# foc.net
KiCad netlist of a schematic drawn in EasyEDA Pro
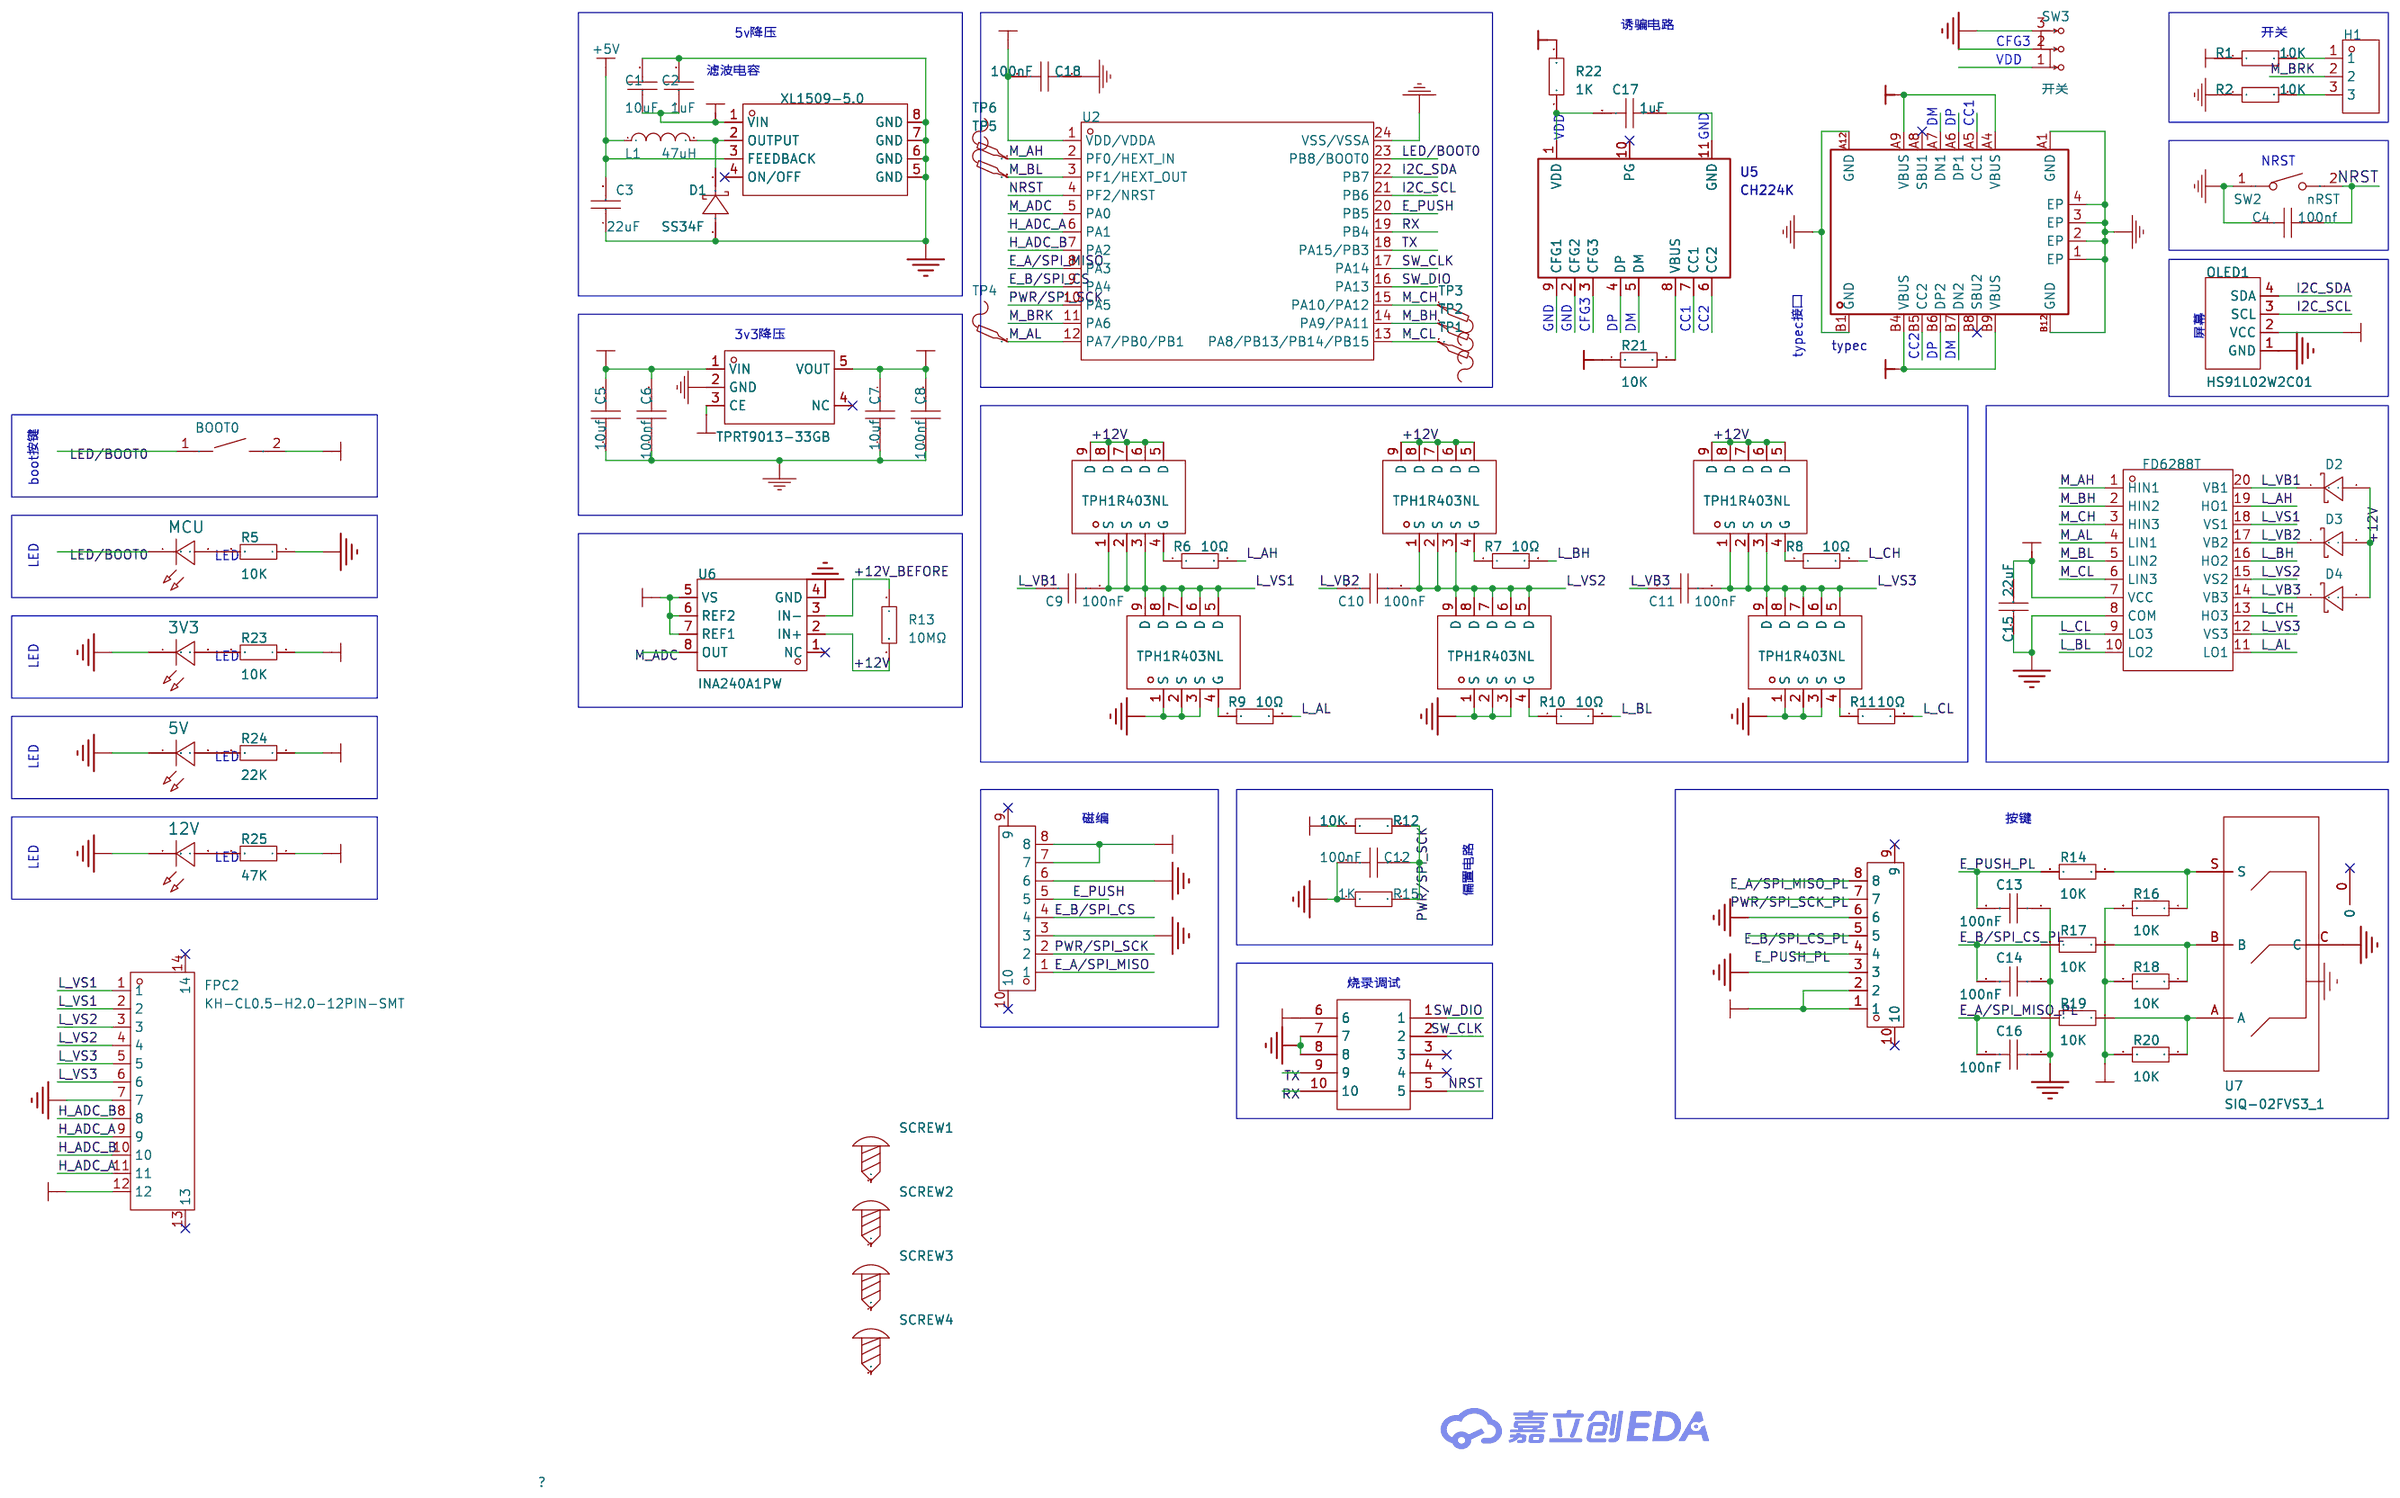
[diagram p0: schematic sheet]

(export (version "E")
  (design (tool "Eeschema 10.0.6"))
  (components
    (comp (ref "3V3")
      (value "~")
      (footprint "easyedapro:LED_0603")
      (libsource (lib "easyedapro") (part "LED_R"))
    )
    (comp (ref "5V")
      (value "~")
      (footprint "easyedapro:LED_0603")
      (libsource (lib "easyedapro") (part "LED_R"))
    )
    (comp (ref "12V")
      (value "~")
      (footprint "easyedapro:LED_0603")
      (libsource (lib "easyedapro") (part "LED_R"))
    )
    (comp (ref "BOOT0")
      (value "轻触按键3*4*H")
      (footprint "easyedapro:SW-SMD_L4.0-W2.9-LS5.0")
      (libsource (lib "") (part "轻触按键3*4*H_1"))
    )
    (comp (ref "C1")
      (value "10uF")
      (footprint "easyedapro:C1206")
      (description "容值:10uF;精度:±10%;额定电压:50V;材质(温度系数):X5R;")
      (fields
        (field (name "Manufacturer Part") "CL31A106KBHNNNE")
        (field (name "Manufacturer") "SAMSUNG(三星)")
      )
      (libsource (lib "easyedapro") (part "CL31A106KBHNNNE"))
    )
    (comp (ref "C2")
      (value "1uF")
      (fields
        (field (name "Manufacturer Part") "CL10A105KB8NNNC")
        (field (name "Manufacturer") "SAMSUNG(三星)")
      )
      (libsource (lib "easyedapro") (part "cl21b105kbfnnne"))
    )
    (comp (ref "C3")
      (value "22uF")
      (fields
        (field (name "Manufacturer Part") "CGA1206X5R226M350NT")
        (field (name "Manufacturer") "HRE(芯声)")
      )
      (libsource (lib "easyedapro") (part "cl21a476mqynnne"))
    )
    (comp (ref "C4")
      (value "100nf")
      (footprint "easyedapro:C0603")
      (libsource (lib "easyedapro") (part "100nf"))
    )
    (comp (ref "C5")
      (value "10uf")
      (footprint "easyedapro:C1206")
      (description "容值:10uF;精度:±10%;额定电压:50V;温度系数:X5R;")
      (fields
        (field (name "Manufacturer Part") "HGC1206R5106K500NSPJ")
        (field (name "Manufacturer") "Chinocera(华瓷)")
      )
      (libsource (lib "easyedapro") (part "HGC1206R5106K500NSPJ"))
    )
    (comp (ref "C6")
      (value "100nf")
      (footprint "easyedapro:C0603")
      (libsource (lib "easyedapro") (part "100nf"))
    )
    (comp (ref "C7")
      (value "10uf")
      (footprint "easyedapro:C1206")
      (description "容值:10uF;精度:±10%;额定电压:50V;温度系数:X5R;")
      (fields
        (field (name "Manufacturer Part") "HGC1206R5106K500NSPJ")
        (field (name "Manufacturer") "Chinocera(华瓷)")
      )
      (libsource (lib "easyedapro") (part "HGC1206R5106K500NSPJ"))
    )
    (comp (ref "C8")
      (value "100nf")
      (footprint "easyedapro:C0603")
      (libsource (lib "easyedapro") (part "100nf"))
    )
    (comp (ref "C9")
      (value "100nF")
      (footprint "easyedapro:C0603")
      (description "容值:100nF;精度:±10%;额定电压:50V;材质(温度系数):X7R;")
      (fields
        (field (name "Manufacturer Part") "CC0603KRX7R9BB104")
        (field (name "Manufacturer") "YAGEO(国巨)")
      )
      (libsource (lib "easyedapro") (part "CC0603KRX7R9BB104"))
    )
    (comp (ref "C10")
      (value "100nF")
      (footprint "easyedapro:C0603")
      (description "容值:100nF;精度:±10%;额定电压:50V;材质(温度系数):X7R;")
      (fields
        (field (name "Manufacturer Part") "CC0603KRX7R9BB104")
        (field (name "Manufacturer") "YAGEO(国巨)")
      )
      (libsource (lib "easyedapro") (part "CC0603KRX7R9BB104"))
    )
    (comp (ref "C11")
      (value "100nF")
      (footprint "easyedapro:C0603")
      (description "容值:100nF;精度:±10%;额定电压:50V;材质(温度系数):X7R;")
      (fields
        (field (name "Manufacturer Part") "CC0603KRX7R9BB104")
        (field (name "Manufacturer") "YAGEO(国巨)")
      )
      (libsource (lib "easyedapro") (part "CC0603KRX7R9BB104"))
    )
    (comp (ref "C12")
      (value "100nF")
      (footprint "easyedapro:C0603")
      (libsource (lib "easyedapro") (part "CapAcitance"))
    )
    (comp (ref "C13")
      (value "100nF")
      (footprint "easyedapro:C0603")
      (libsource (lib "easyedapro") (part "CapAcitance"))
    )
    (comp (ref "C14")
      (value "100nF")
      (footprint "easyedapro:C0603")
      (libsource (lib "easyedapro") (part "CapAcitance"))
    )
    (comp (ref "C15")
      (value "22uF")
      (fields
        (field (name "Manufacturer Part") "CGA0805X5R226M350MT")
        (field (name "Manufacturer") "HRE(芯声)")
      )
      (libsource (lib "easyedapro") (part "cc0805krx7r9bb104"))
    )
    (comp (ref "C16")
      (value "100nF")
      (footprint "easyedapro:C0603")
      (libsource (lib "easyedapro") (part "CapAcitance"))
    )
    (comp (ref "C17")
      (value "1uF")
      (footprint "easyedapro:C0603")
      (libsource (lib "easyedapro") (part "CapAcitance"))
    )
    (comp (ref "C18")
      (value "100nF")
      (footprint "easyedapro:C0603")
      (libsource (lib "easyedapro") (part "CapAcitance"))
    )
    (comp (ref "D1")
      (value "SS34F")
      (footprint "easyedapro:SMAF_L3.5-W2.6-LS4.7-FD")
      (description "二极管配置:独立式;正向压降(Vf):550mV@3A;直流反向耐压(Vr):40V;平均整流电流(Io):3A;")
      (fields (field (name "Manufacturer") "FUXINSEMI(富芯森美)"))
      (libsource (lib "easyedapro") (part "SS34F_C908239"))
    )
    (comp (ref "D2")
      (value "1N5819WS")
      (footprint "easyedapro:SOD-323_L1.8-W1.3-LS2.5-RD")
      (description "正向压降(Vf):600mV@1A;直流反向耐压(Vr):40V;平均整流电流(Io):1A;")
      (fields (field (name "Manufacturer") "Hottech(合科泰)"))
      (libsource (lib "easyedapro") (part "1N5819WS"))
    )
    (comp (ref "D3")
      (value "1N5819WS")
      (footprint "easyedapro:SOD-323_L1.8-W1.3-LS2.5-RD")
      (description "正向压降(Vf):600mV@1A;直流反向耐压(Vr):40V;平均整流电流(Io):1A;")
      (fields (field (name "Manufacturer") "Hottech(合科泰)"))
      (libsource (lib "easyedapro") (part "1N5819WS"))
    )
    (comp (ref "D4")
      (value "1N5819WS")
      (footprint "easyedapro:SOD-323_L1.8-W1.3-LS2.5-RD")
      (description "正向压降(Vf):600mV@1A;直流反向耐压(Vr):40V;平均整流电流(Io):1A;")
      (fields (field (name "Manufacturer") "Hottech(合科泰)"))
      (libsource (lib "easyedapro") (part "1N5819WS"))
    )
    (comp (ref "FPC1")
      (value "FPC-05F-8PH20")
      (footprint "easyedapro:FPC-SMD_8P-P0.50_FPC-05F-8PH20")
      (description "锁定特性:翻盖式;触点类型:下接;触点数量:8P;间距:0.5mm;安装类型:卧贴;工作温度范围:-25°C~+85°C;")
      (fields (field (name "Manufacturer") "XUNPU(讯普)"))
      (libsource (lib "easyedapro") (part "FPC-05F-8PH20"))
    )
    (comp (ref "FPC2")
      (value "KH-CL0.5-H2.0-12PIN-SMT")
      (footprint "easyedapro:FPC-SMD_12P-P0.50_KH-CL0.5-H2.0-12PIN-SMT")
      (description "锁定特性:抽屉式;触点类型:下接;触点数量:12P;间距:0.5mm;")
      (fields (field (name "Manufacturer") "kinghelm(金航标)"))
      (libsource (lib "easyedapro") (part "KH-CL0.5-H2.0-12PIN-SMT"))
    )
    (comp (ref "FPC3")
      (value "FPC-05F-8PH20")
      (footprint "easyedapro:FPC-SMD_8P-P0.50_FPC-05F-8PH20")
      (description "锁定特性:翻盖式;触点类型:下接;触点数量:8P;间距:0.5mm;安装类型:卧贴;工作温度范围:-25°C~+85°C;")
      (fields (field (name "Manufacturer") "XUNPU(讯普)"))
      (libsource (lib "easyedapro") (part "FPC-05F-8PH20"))
    )
    (comp (ref "H1")
      (value "~")
      (footprint "easyedapro:HDR-TH_3P-P2.54-V-M")
      (libsource (lib "easyedapro") (part "PZ254V-11-03P_C2937625"))
    )
    (comp (ref "L1")
      (value "47uH")
      (fields (field (name "Manufacturer Part") "FXL0630-470-M") (field (name "Manufacturer") "cjiang(长江微电)"))
      (libsource (lib "easyedapro") (part "mscd32-470kt"))
    )
    (comp (ref "MCU")
      (value "~")
      (footprint "easyedapro:LED_0603")
      (libsource (lib "easyedapro") (part "LED_R"))
    )
    (comp (ref "OLED1")
      (value "HS91L02W2C01")
      (footprint "easyedapro:OLED-TH_L38.0-W12.0_HS91L02W2C01")
      (description "主控芯片:SSD1306;接口类型:I2C;尺寸(inch):0.91;像素分辨率:128x32;")
      (fields (field (name "Manufacturer") "HS(汉昇)"))
      (libsource (lib "easyedapro") (part "HS91L02W2C01"))
    )
    (comp (ref "P1")
      (value "~")
      (footprint "easyedapro:PAD_S_2.54_2*5")
      (libsource (lib "easyedapro") (part "PAD_S_2.54_2*5"))
    )
    (comp (ref "Q1")
      (value "TPH1R403NL")
      (footprint "easyedapro:DSOP-8_L5.0-W5.0-P1.27-LS6.0-BL-EP")
      (fields (field (name "Manufacturer") "TOSHIBA(东芝)"))
      (libsource (lib "easyedapro") (part "TPH1R403NL"))
    )
    (comp (ref "Q2")
      (value "TPH1R403NL")
      (footprint "easyedapro:DSOP-8_L5.0-W5.0-P1.27-LS6.0-BL-EP")
      (fields (field (name "Manufacturer") "TOSHIBA(东芝)"))
      (libsource (lib "easyedapro") (part "TPH1R403NL"))
    )
    (comp (ref "Q3")
      (value "TPH1R403NL")
      (footprint "easyedapro:DSOP-8_L5.0-W5.0-P1.27-LS6.0-BL-EP")
      (fields (field (name "Manufacturer") "TOSHIBA(东芝)"))
      (libsource (lib "easyedapro") (part "TPH1R403NL"))
    )
    (comp (ref "Q4")
      (value "TPH1R403NL")
      (footprint "easyedapro:DSOP-8_L5.0-W5.0-P1.27-LS6.0-BL-EP")
      (fields (field (name "Manufacturer") "TOSHIBA(东芝)"))
      (libsource (lib "easyedapro") (part "TPH1R403NL"))
    )
    (comp (ref "Q5")
      (value "TPH1R403NL")
      (footprint "easyedapro:DSOP-8_L5.0-W5.0-P1.27-LS6.0-BL-EP")
      (fields (field (name "Manufacturer") "TOSHIBA(东芝)"))
      (libsource (lib "easyedapro") (part "TPH1R403NL"))
    )
    (comp (ref "Q6")
      (value "TPH1R403NL")
      (footprint "easyedapro:DSOP-8_L5.0-W5.0-P1.27-LS6.0-BL-EP")
      (fields (field (name "Manufacturer") "TOSHIBA(东芝)"))
      (libsource (lib "easyedapro") (part "TPH1R403NL"))
    )
    (comp (ref "R1") (value "10K") (footprint "easyedapro:R0603") (libsource (lib "easyedapro") (part "电阻")))
    (comp (ref "R2") (value "10K") (footprint "easyedapro:R0603") (libsource (lib "easyedapro") (part "电阻")))
    (comp (ref "R5") (value "10K") (footprint "easyedapro:R0603") (libsource (lib "easyedapro") (part "电阻")))
    (comp (ref "R6")
      (value "10Ω")
      (footprint "easyedapro:R0603")
      (description "电阻类型:厚膜电阻;阻值:10Ω;精度:±1%;功率:100mW;最大工作电压:75V;温度系数:±400ppm/°C;")
      (fields
        (field (name "Manufacturer Part") "0603WAF100JT5E")
        (field (name "Manufacturer") "UNI-ROYAL(厚声)")
      )
      (libsource (lib "easyedapro") (part "0603WAF100JT5E"))
    )
    (comp (ref "R7")
      (value "10Ω")
      (footprint "easyedapro:R0603")
      (description "电阻类型:厚膜电阻;阻值:10Ω;精度:±1%;功率:100mW;最大工作电压:75V;温度系数:±400ppm/°C;")
      (fields
        (field (name "Manufacturer Part") "0603WAF100JT5E")
        (field (name "Manufacturer") "UNI-ROYAL(厚声)")
      )
      (libsource (lib "easyedapro") (part "0603WAF100JT5E"))
    )
    (comp (ref "R8")
      (value "10Ω")
      (footprint "easyedapro:R0603")
      (description "电阻类型:厚膜电阻;阻值:10Ω;精度:±1%;功率:100mW;最大工作电压:75V;温度系数:±400ppm/°C;")
      (fields
        (field (name "Manufacturer Part") "0603WAF100JT5E")
        (field (name "Manufacturer") "UNI-ROYAL(厚声)")
      )
      (libsource (lib "easyedapro") (part "0603WAF100JT5E"))
    )
    (comp (ref "R9")
      (value "10Ω")
      (footprint "easyedapro:R0603")
      (description "电阻类型:厚膜电阻;阻值:10Ω;精度:±1%;功率:100mW;最大工作电压:75V;温度系数:±400ppm/°C;")
      (fields
        (field (name "Manufacturer Part") "0603WAF100JT5E")
        (field (name "Manufacturer") "UNI-ROYAL(厚声)")
      )
      (libsource (lib "easyedapro") (part "0603WAF100JT5E"))
    )
    (comp (ref "R10")
      (value "10Ω")
      (footprint "easyedapro:R0603")
      (description "电阻类型:厚膜电阻;阻值:10Ω;精度:±1%;功率:100mW;最大工作电压:75V;温度系数:±400ppm/°C;")
      (fields
        (field (name "Manufacturer Part") "0603WAF100JT5E")
        (field (name "Manufacturer") "UNI-ROYAL(厚声)")
      )
      (libsource (lib "easyedapro") (part "0603WAF100JT5E"))
    )
    (comp (ref "R11")
      (value "10Ω")
      (footprint "easyedapro:R0603")
      (description "电阻类型:厚膜电阻;阻值:10Ω;精度:±1%;功率:100mW;最大工作电压:75V;温度系数:±400ppm/°C;")
      (fields
        (field (name "Manufacturer Part") "0603WAF100JT5E")
        (field (name "Manufacturer") "UNI-ROYAL(厚声)")
      )
      (libsource (lib "easyedapro") (part "0603WAF100JT5E"))
    )
    (comp (ref "R12") (value "10K") (footprint "easyedapro:R0603") (libsource (lib "easyedapro") (part "电阻")))
    (comp (ref "R13")
      (value "10MΩ")
      (footprint "easyedapro:R2512")
      (description "电阻类型:厚膜电阻;阻值:10MΩ;精度:±5%;功率:1W;工作电压:200V;温度系数:±100ppm/°C;")
      (fields
        (field (name "Manufacturer Part") "CR2512J10M0E04Z")
        (field (name "Manufacturer") "EVER OHMS(天二科技)")
      )
      (libsource (lib "easyedapro") (part "CR2512J10ME04"))
    )
    (comp (ref "R14")
      (value "10K")
      (footprint "easyedapro:R0603")
      (fields (field (name "Manufacturer Part") "ARG03FTC1002") (field (name "Manufacturer") "Viking Tech"))
      (libsource (lib "easyedapro") (part "10K"))
    )
    (comp (ref "R15") (value "1K") (footprint "easyedapro:R0603") (libsource (lib "easyedapro") (part "电阻")))
    (comp (ref "R16")
      (value "10K")
      (footprint "easyedapro:R0603")
      (fields (field (name "Manufacturer Part") "ARG03FTC1002") (field (name "Manufacturer") "Viking Tech"))
      (libsource (lib "easyedapro") (part "10K"))
    )
    (comp (ref "R17")
      (value "10K")
      (footprint "easyedapro:R0603")
      (fields (field (name "Manufacturer Part") "ARG03FTC1002") (field (name "Manufacturer") "Viking Tech"))
      (libsource (lib "easyedapro") (part "10K"))
    )
    (comp (ref "R18")
      (value "10K")
      (footprint "easyedapro:R0603")
      (fields (field (name "Manufacturer Part") "ARG03FTC1002") (field (name "Manufacturer") "Viking Tech"))
      (libsource (lib "easyedapro") (part "10K"))
    )
    (comp (ref "R19")
      (value "10K")
      (footprint "easyedapro:R0603")
      (fields (field (name "Manufacturer Part") "ARG03FTC1002") (field (name "Manufacturer") "Viking Tech"))
      (libsource (lib "easyedapro") (part "10K"))
    )
    (comp (ref "R20")
      (value "10K")
      (footprint "easyedapro:R0603")
      (fields (field (name "Manufacturer Part") "ARG03FTC1002") (field (name "Manufacturer") "Viking Tech"))
      (libsource (lib "easyedapro") (part "10K"))
    )
    (comp (ref "R21") (value "10K") (footprint "easyedapro:R0603") (libsource (lib "easyedapro") (part "电阻")))
    (comp (ref "R22") (value "1K") (footprint "easyedapro:R0603") (libsource (lib "easyedapro") (part "电阻")))
    (comp (ref "R23") (value "10K") (footprint "easyedapro:R0603") (libsource (lib "easyedapro") (part "电阻")))
    (comp (ref "R24") (value "22K") (footprint "easyedapro:R0603") (libsource (lib "easyedapro") (part "电阻")))
    (comp (ref "R25") (value "47K") (footprint "easyedapro:R0603") (libsource (lib "easyedapro") (part "电阻")))
    (comp (ref "SCREW1")
      (value "~")
      (footprint "easyedapro:M2螺丝")
      (libsource (lib "easyedapro") (part "螺丝孔"))
    )
    (comp (ref "SCREW2")
      (value "~")
      (footprint "easyedapro:M2螺丝")
      (libsource (lib "easyedapro") (part "螺丝孔"))
    )
    (comp (ref "SCREW3")
      (value "~")
      (footprint "easyedapro:M2螺丝")
      (libsource (lib "easyedapro") (part "螺丝孔"))
    )
    (comp (ref "SCREW4")
      (value "~")
      (footprint "easyedapro:M2螺丝")
      (libsource (lib "easyedapro") (part "螺丝孔"))
    )
    (comp (ref "SW2")
      (value "nRST")
      (fields (field (name "Manufacturer Part") "轻触按键3*4*H"))
      (libsource (lib "easyedapro") (part "轻触按键3*4*H"))
    )
    (comp (ref "SW3")
      (value "开关")
      (footprint "easyedapro:SW-TH_SS-12D01-GX")
      (libsource (lib "easyedapro") (part "开关"))
    )
    (comp (ref "TP1")
      (value "~")
      (footprint "easyedapro:Test-Point-0.5mm")
      (description "Test Point 测试点")
      (libsource (lib "easyedapro") (part "Test-Point"))
    )
    (comp (ref "TP2")
      (value "~")
      (footprint "easyedapro:Test-Point-0.5mm")
      (description "Test Point 测试点")
      (libsource (lib "easyedapro") (part "Test-Point"))
    )
    (comp (ref "TP3")
      (value "~")
      (footprint "easyedapro:Test-Point-0.5mm")
      (description "Test Point 测试点")
      (libsource (lib "easyedapro") (part "Test-Point"))
    )
    (comp (ref "TP4")
      (value "~")
      (footprint "easyedapro:Test-Point-0.5mm")
      (description "Test Point 测试点")
      (libsource (lib "easyedapro") (part "Test-Point"))
    )
    (comp (ref "TP5")
      (value "~")
      (footprint "easyedapro:Test-Point-0.5mm")
      (description "Test Point 测试点")
      (libsource (lib "easyedapro") (part "Test-Point"))
    )
    (comp (ref "TP6")
      (value "~")
      (footprint "easyedapro:Test-Point-0.5mm")
      (description "Test Point 测试点")
      (libsource (lib "easyedapro") (part "Test-Point"))
    )
    (comp (ref "U1")
      (value "XL1509-5.0")
      (footprint "easyedapro:SOIC-8_L4.9-W3.9-P1.27-LS6.0-TR")
      (fields (field (name "Manufacturer") "UMW(广东友台半导体)"))
      (libsource (lib "easyedapro") (part "XL1509-5.0_C2902368"))
    )
    (comp (ref "U2")
      (value "~")
      (footprint "easyedapro:TSSOP-24_L7.8-W4.4-P0.65-LS6.4-BL")
      (fields (field (name "Manufacturer") "Artery Technology"))
      (libsource (lib "easyedapro") (part "AT32M416ExP7"))
    )
    (comp (ref "U4")
      (value "TPRT9013-33GB")
      (footprint "easyedapro:SOT-23-5_L3.0-W1.7-P0.95-LS2.8-BL")
      (description "输出类型:-;")
      (fields (field (name "Manufacturer") "TECH PUBLIC(台舟)"))
      (libsource (lib "easyedapro") (part "TPRT9013-33GB"))
    )
    (comp (ref "U5")
      (value "CH224K")
      (footprint "easyedapro:ESSOP-10_L4.9-W3.9-P1.0-LS6.0-TL-EP")
      (fields (field (name "Manufacturer") "WCH(南京沁恒)"))
      (libsource (lib "easyedapro") (part "CH224K"))
    )
    (comp (ref "U6")
      (value "INA240A1PW")
      (footprint "easyedapro:TSSOP-8_L4.4-W3.0-P0.65-LS6.4-TL")
      (description "放大器数:单路;")
      (fields (field (name "Manufacturer") "TI(德州仪器)"))
      (libsource (lib "easyedapro") (part "INA240A1PW"))
    )
    (comp (ref "U7")
      (value "SIQ-02FVS3_1")
      (footprint "easyedapro:SW-SMD_SIQ-02FVS3_1")
      (libsource (lib "easyedapro") (part "SIQ-02FVS3_1"))
    )
    (comp (ref "U8")
      (value "FD6288T")
      (footprint "easyedapro:TSSOP-20_L6.5-W4.4-P0.65-LS6.4-BL")
      (description "驱动配置:高低侧;负载类型:MOSFET;峰值灌电流:1.5A;峰值拉电流:1.8A;电源电压:8V~20V;")
      (fields (field (name "Manufacturer") "JSMSEMI(杰盛微)"))
      (libsource (lib "easyedapro") (part "FD6288T"))
    )
    (comp (ref "USB1")
      (value "typec")
      (footprint "easyedapro:USB-C-SMD_KH-TYPE-C-16P")
      (libsource (lib "easyedapro") (part "TYPEC_C9900016956"))
    )
  )
  (nets
    (net (code "1") (name "+3V3") (class "Default")
      (node (ref "BOOT0") (pin "2") (pinfunction "2_2") (pintype "unspecified"))
      (node (ref "C18") (pin "1") (pinfunction "1_1") (pintype "input"))
      (node (ref "C7") (pin "1") (pinfunction "1_1") (pintype "unspecified"))
      (node (ref "C8") (pin "2") (pinfunction "2_2") (pintype "unspecified"))
      (node (ref "FPC1") (pin "7") (pinfunction "7_7") (pintype "unspecified"))
      (node (ref "FPC1") (pin "8") (pinfunction "8_8") (pintype "unspecified"))
      (node (ref "FPC2") (pin "12") (pinfunction "12_12") (pintype "unspecified"))
      (node (ref "OLED1") (pin "2") (pinfunction "VCC_2") (pintype "unspecified"))
      (node (ref "P1") (pin "6") (pinfunction "6_6") (pintype "input"))
      (node (ref "R1") (pin "1") (pinfunction "1_1") (pintype "input"))
      (node (ref "R23") (pin "1") (pinfunction "1_1") (pintype "input"))
      (node (ref "U2") (pin "1") (pinfunction "VDD/VDDA_1") (pintype "input"))
      (node (ref "U4") (pin "5") (pinfunction "VOUT_5") (pintype "input"))
      (node (ref "U6") (pin "5") (pinfunction "VS_5") (pintype "unspecified"))
      (node (ref "U6") (pin "6") (pinfunction "REF2_6") (pintype "unspecified"))
      (node (ref "U6") (pin "7") (pinfunction "REF1_7") (pintype "unspecified"))
    )
    (net (code "2") (name "+3V3_PL") (class "Default")
      (node (ref "FPC3") (pin "1") (pinfunction "1_1") (pintype "unspecified"))
      (node (ref "FPC3") (pin "2") (pinfunction "2_2") (pintype "unspecified"))
      (node (ref "R16") (pin "2") (pinfunction "2_2") (pintype "unspecified"))
      (node (ref "R18") (pin "2") (pinfunction "2_2") (pintype "unspecified"))
      (node (ref "R20") (pin "2") (pinfunction "2_2") (pintype "unspecified"))
    )
    (net (code "3") (name "+5V") (class "Default")
      (node (ref "C3") (pin "2") (pinfunction "2_2") (pintype "input"))
      (node (ref "C5") (pin "1") (pinfunction "1_1") (pintype "unspecified"))
      (node (ref "C6") (pin "2") (pinfunction "2_2") (pintype "unspecified"))
      (node (ref "L1") (pin "1") (pinfunction "1_1") (pintype "unspecified"))
      (node (ref "R24") (pin "1") (pinfunction "1_1") (pintype "input"))
      (node (ref "U1") (pin "3") (pinfunction "FEEDBACK_3") (pintype "unspecified"))
      (node (ref "U4") (pin "1") (pinfunction "VIN_1") (pintype "input"))
      (node (ref "U4") (pin "3") (pinfunction "CE_3") (pintype "input"))
    )
    (net (code "4") (name "+12V") (class "Default")
      (node (ref "C1") (pin "1") (pinfunction "1_1") (pintype "input"))
      (node (ref "C15") (pin "2") (pinfunction "2_2") (pintype "input"))
      (node (ref "C2") (pin "1") (pinfunction "1_1") (pintype "input"))
      (node (ref "D2") (pin "2") (pinfunction "A_2") (pintype "unspecified"))
      (node (ref "D3") (pin "2") (pinfunction "A_2") (pintype "unspecified"))
      (node (ref "D4") (pin "2") (pinfunction "A_2") (pintype "unspecified"))
      (node (ref "Q1") (pin "5") (pinfunction "D_5") (pintype "unspecified"))
      (node (ref "Q1") (pin "6") (pinfunction "D_6") (pintype "unspecified"))
      (node (ref "Q1") (pin "7") (pinfunction "D_7") (pintype "unspecified"))
      (node (ref "Q1") (pin "8") (pinfunction "D_8") (pintype "unspecified"))
      (node (ref "Q1") (pin "9") (pinfunction "D_9") (pintype "unspecified"))
      (node (ref "Q2") (pin "5") (pinfunction "D_5") (pintype "unspecified"))
      (node (ref "Q2") (pin "6") (pinfunction "D_6") (pintype "unspecified"))
      (node (ref "Q2") (pin "7") (pinfunction "D_7") (pintype "unspecified"))
      (node (ref "Q2") (pin "8") (pinfunction "D_8") (pintype "unspecified"))
      (node (ref "Q2") (pin "9") (pinfunction "D_9") (pintype "unspecified"))
      (node (ref "Q3") (pin "5") (pinfunction "D_5") (pintype "unspecified"))
      (node (ref "Q3") (pin "6") (pinfunction "D_6") (pintype "unspecified"))
      (node (ref "Q3") (pin "7") (pinfunction "D_7") (pintype "unspecified"))
      (node (ref "Q3") (pin "8") (pinfunction "D_8") (pintype "unspecified"))
      (node (ref "Q3") (pin "9") (pinfunction "D_9") (pintype "unspecified"))
      (node (ref "R12") (pin "1") (pinfunction "1_1") (pintype "input"))
      (node (ref "R13") (pin "2") (pinfunction "2_2") (pintype "unspecified"))
      (node (ref "R25") (pin "1") (pinfunction "1_1") (pintype "input"))
      (node (ref "U1") (pin "1") (pinfunction "VIN_1") (pintype "unspecified"))
      (node (ref "U6") (pin "2") (pinfunction "IN+_2") (pintype "unspecified"))
      (node (ref "U8") (pin "7") (pinfunction "VCC_7") (pintype "unspecified"))
    )
    (net (code "5") (name "+12V_BEFORE") (class "Default")
      (node (ref "R13") (pin "1") (pinfunction "1_1") (pintype "unspecified"))
      (node (ref "R21") (pin "1") (pinfunction "1_1") (pintype "input"))
      (node (ref "R22") (pin "2") (pinfunction "2_2") (pintype "input"))
      (node (ref "U6") (pin "3") (pinfunction "IN-_3") (pintype "unspecified"))
      (node (ref "USB1") (pin "A4") (pinfunction "VBUS_A4") (pintype "unspecified"))
      (node (ref "USB1") (pin "A9") (pinfunction "VBUS_A9") (pintype "unspecified"))
      (node (ref "USB1") (pin "B4") (pinfunction "VBUS_B4") (pintype "unspecified"))
      (node (ref "USB1") (pin "B9") (pinfunction "VBUS_B9") (pintype "unspecified"))
    )
    (net (code "6") (name "/CC1") (class "Default")
      (node (ref "U5") (pin "7") (pinfunction "CC1_7") (pintype "unspecified"))
      (node (ref "USB1") (pin "A5") (pinfunction "CC1_A5") (pintype "unspecified"))
    )
    (net (code "7") (name "/CC2") (class "Default")
      (node (ref "U5") (pin "6") (pinfunction "CC2_6") (pintype "unspecified"))
      (node (ref "USB1") (pin "B5") (pinfunction "CC2_B5") (pintype "unspecified"))
    )
    (net (code "8") (name "/CFG3") (class "Default")
      (node (ref "SW3") (pin "2") (pinfunction "2_2") (pintype "unspecified"))
      (node (ref "U5") (pin "3") (pinfunction "CFG3_3") (pintype "unspecified"))
    )
    (net (code "9") (name "/DM") (class "Default")
      (node (ref "U5") (pin "5") (pinfunction "DM_5") (pintype "unspecified"))
      (node (ref "USB1") (pin "A7") (pinfunction "DN1_A7") (pintype "unspecified"))
      (node (ref "USB1") (pin "B7") (pinfunction "DN2_B7") (pintype "unspecified"))
    )
    (net (code "10") (name "/DP") (class "Default")
      (node (ref "U5") (pin "4") (pinfunction "DP_4") (pintype "unspecified"))
      (node (ref "USB1") (pin "A6") (pinfunction "DP1_A6") (pintype "unspecified"))
      (node (ref "USB1") (pin "B6") (pinfunction "DP2_B6") (pintype "unspecified"))
    )
    (net (code "11") (name "/E_A{slash}SPI_MISO") (class "Default")
      (node (ref "FPC1") (pin "1") (pinfunction "1_1") (pintype "unspecified"))
      (node (ref "U2") (pin "8") (pinfunction "PA3_8") (pintype "input"))
    )
    (net (code "12") (name "/E_A{slash}SPI_MISO_PL") (class "Default")
      (node (ref "C16") (pin "2") (pinfunction "2_2") (pintype "input"))
      (node (ref "FPC3") (pin "8") (pinfunction "8_8") (pintype "unspecified"))
      (node (ref "R19") (pin "2") (pinfunction "2_2") (pintype "unspecified"))
    )
    (net (code "13") (name "/E_B{slash}SPI_CS") (class "Default")
      (node (ref "FPC1") (pin "4") (pinfunction "4_4") (pintype "unspecified"))
      (node (ref "U2") (pin "9") (pinfunction "PA4_9") (pintype "input"))
    )
    (net (code "14") (name "/E_B{slash}SPI_CS_PL") (class "Default")
      (node (ref "C14") (pin "2") (pinfunction "2_2") (pintype "input"))
      (node (ref "FPC3") (pin "5") (pinfunction "5_5") (pintype "unspecified"))
      (node (ref "R17") (pin "2") (pinfunction "2_2") (pintype "unspecified"))
    )
    (net (code "15") (name "/E_PUSH") (class "Default")
      (node (ref "FPC1") (pin "5") (pinfunction "5_5") (pintype "unspecified"))
      (node (ref "U2") (pin "20") (pinfunction "PB5_20") (pintype "input"))
    )
    (net (code "16") (name "/E_PUSH_PL") (class "Default")
      (node (ref "C13") (pin "2") (pinfunction "2_2") (pintype "input"))
      (node (ref "FPC3") (pin "4") (pinfunction "4_4") (pintype "unspecified"))
      (node (ref "R14") (pin "2") (pinfunction "2_2") (pintype "unspecified"))
    )
    (net (code "17") (name "/H_ADC_A") (class "Default")
      (node (ref "FPC2") (pin "11") (pinfunction "11_11") (pintype "unspecified"))
      (node (ref "FPC2") (pin "9") (pinfunction "9_9") (pintype "unspecified"))
      (node (ref "U2") (pin "6") (pinfunction "PA1_6") (pintype "input"))
    )
    (net (code "18") (name "/H_ADC_B") (class "Default")
      (node (ref "FPC2") (pin "10") (pinfunction "10_10") (pintype "unspecified"))
      (node (ref "FPC2") (pin "8") (pinfunction "8_8") (pintype "unspecified"))
      (node (ref "U2") (pin "7") (pinfunction "PA2_7") (pintype "input"))
    )
    (net (code "19") (name "/I2C_SCL") (class "Default")
      (node (ref "OLED1") (pin "3") (pinfunction "SCL_3") (pintype "unspecified"))
      (node (ref "U2") (pin "21") (pinfunction "PB6_21") (pintype "input"))
    )
    (net (code "20") (name "/I2C_SDA") (class "Default")
      (node (ref "OLED1") (pin "4") (pinfunction "SDA_4") (pintype "unspecified"))
      (node (ref "U2") (pin "22") (pinfunction "PB7_22") (pintype "input"))
    )
    (net (code "21") (name "/LED{slash}BOOT0") (class "Default")
      (node (ref "BOOT0") (pin "1") (pinfunction "1_1") (pintype "unspecified"))
      (node (ref "MCU") (pin "1") (pinfunction "C_1") (pintype "input"))
      (node (ref "U2") (pin "23") (pinfunction "PB8/BOOT0_23") (pintype "input"))
    )
    (net (code "22") (name "/L_AH") (class "Default")
      (node (ref "R6") (pin "2") (pinfunction "2_2") (pintype "input"))
      (node (ref "U8") (pin "19") (pinfunction "HO1_19") (pintype "unspecified"))
    )
    (net (code "23") (name "/L_AL") (class "Default")
      (node (ref "R9") (pin "2") (pinfunction "2_2") (pintype "input"))
      (node (ref "U8") (pin "11") (pinfunction "LO1_11") (pintype "unspecified"))
    )
    (net (code "24") (name "/L_BH") (class "Default")
      (node (ref "R7") (pin "2") (pinfunction "2_2") (pintype "input"))
      (node (ref "U8") (pin "16") (pinfunction "HO2_16") (pintype "unspecified"))
    )
    (net (code "25") (name "/L_BL") (class "Default")
      (node (ref "R10") (pin "2") (pinfunction "2_2") (pintype "input"))
      (node (ref "U8") (pin "10") (pinfunction "LO2_10") (pintype "unspecified"))
    )
    (net (code "26") (name "/L_CH") (class "Default")
      (node (ref "R8") (pin "2") (pinfunction "2_2") (pintype "input"))
      (node (ref "U8") (pin "13") (pinfunction "HO3_13") (pintype "unspecified"))
    )
    (net (code "27") (name "/L_CL") (class "Default")
      (node (ref "R11") (pin "2") (pinfunction "2_2") (pintype "input"))
      (node (ref "U8") (pin "9") (pinfunction "LO3_9") (pintype "unspecified"))
    )
    (net (code "28") (name "/L_VB1") (class "Default")
      (node (ref "C9") (pin "1") (pinfunction "1_1") (pintype "unspecified"))
      (node (ref "D2") (pin "1") (pinfunction "K_1") (pintype "unspecified"))
      (node (ref "U8") (pin "20") (pinfunction "VB1_20") (pintype "unspecified"))
    )
    (net (code "29") (name "/L_VB2") (class "Default")
      (node (ref "C10") (pin "1") (pinfunction "1_1") (pintype "unspecified"))
      (node (ref "D3") (pin "1") (pinfunction "K_1") (pintype "unspecified"))
      (node (ref "U8") (pin "17") (pinfunction "VB2_17") (pintype "unspecified"))
    )
    (net (code "30") (name "/L_VB3") (class "Default")
      (node (ref "C11") (pin "1") (pinfunction "1_1") (pintype "unspecified"))
      (node (ref "D4") (pin "1") (pinfunction "K_1") (pintype "unspecified"))
      (node (ref "U8") (pin "14") (pinfunction "VB3_14") (pintype "unspecified"))
    )
    (net (code "31") (name "/L_VS1") (class "Default")
      (node (ref "C9") (pin "2") (pinfunction "2_2") (pintype "unspecified"))
      (node (ref "FPC2") (pin "1") (pinfunction "1_1") (pintype "unspecified"))
      (node (ref "FPC2") (pin "2") (pinfunction "2_2") (pintype "unspecified"))
      (node (ref "Q1") (pin "1") (pinfunction "S_1") (pintype "unspecified"))
      (node (ref "Q1") (pin "2") (pinfunction "S_2") (pintype "unspecified"))
      (node (ref "Q1") (pin "3") (pinfunction "S_3") (pintype "unspecified"))
      (node (ref "Q4") (pin "5") (pinfunction "D_5") (pintype "unspecified"))
      (node (ref "Q4") (pin "6") (pinfunction "D_6") (pintype "unspecified"))
      (node (ref "Q4") (pin "7") (pinfunction "D_7") (pintype "unspecified"))
      (node (ref "Q4") (pin "8") (pinfunction "D_8") (pintype "unspecified"))
      (node (ref "Q4") (pin "9") (pinfunction "D_9") (pintype "unspecified"))
      (node (ref "U8") (pin "18") (pinfunction "VS1_18") (pintype "unspecified"))
    )
    (net (code "32") (name "/L_VS2") (class "Default")
      (node (ref "C10") (pin "2") (pinfunction "2_2") (pintype "unspecified"))
      (node (ref "FPC2") (pin "3") (pinfunction "3_3") (pintype "unspecified"))
      (node (ref "FPC2") (pin "4") (pinfunction "4_4") (pintype "unspecified"))
      (node (ref "Q2") (pin "1") (pinfunction "S_1") (pintype "unspecified"))
      (node (ref "Q2") (pin "2") (pinfunction "S_2") (pintype "unspecified"))
      (node (ref "Q2") (pin "3") (pinfunction "S_3") (pintype "unspecified"))
      (node (ref "Q5") (pin "5") (pinfunction "D_5") (pintype "unspecified"))
      (node (ref "Q5") (pin "6") (pinfunction "D_6") (pintype "unspecified"))
      (node (ref "Q5") (pin "7") (pinfunction "D_7") (pintype "unspecified"))
      (node (ref "Q5") (pin "8") (pinfunction "D_8") (pintype "unspecified"))
      (node (ref "Q5") (pin "9") (pinfunction "D_9") (pintype "unspecified"))
      (node (ref "U8") (pin "15") (pinfunction "VS2_15") (pintype "unspecified"))
    )
    (net (code "33") (name "/L_VS3") (class "Default")
      (node (ref "C11") (pin "2") (pinfunction "2_2") (pintype "unspecified"))
      (node (ref "FPC2") (pin "5") (pinfunction "5_5") (pintype "unspecified"))
      (node (ref "FPC2") (pin "6") (pinfunction "6_6") (pintype "unspecified"))
      (node (ref "Q3") (pin "1") (pinfunction "S_1") (pintype "unspecified"))
      (node (ref "Q3") (pin "2") (pinfunction "S_2") (pintype "unspecified"))
      (node (ref "Q3") (pin "3") (pinfunction "S_3") (pintype "unspecified"))
      (node (ref "Q6") (pin "5") (pinfunction "D_5") (pintype "unspecified"))
      (node (ref "Q6") (pin "6") (pinfunction "D_6") (pintype "unspecified"))
      (node (ref "Q6") (pin "7") (pinfunction "D_7") (pintype "unspecified"))
      (node (ref "Q6") (pin "8") (pinfunction "D_8") (pintype "unspecified"))
      (node (ref "Q6") (pin "9") (pinfunction "D_9") (pintype "unspecified"))
      (node (ref "U8") (pin "12") (pinfunction "VS3_12") (pintype "unspecified"))
    )
    (net (code "34") (name "/M_ADC") (class "Default")
      (node (ref "U2") (pin "5") (pinfunction "PA0_5") (pintype "input"))
      (node (ref "U6") (pin "8") (pinfunction "OUT_8") (pintype "unspecified"))
    )
    (net (code "35") (name "/M_AH") (class "Default")
      (node (ref "TP6") (pin "1") (pinfunction "1_1") (pintype "input"))
      (node (ref "U2") (pin "2") (pinfunction "PF0/HEXT_IN_2") (pintype "input"))
      (node (ref "U8") (pin "1") (pinfunction "HIN1_1") (pintype "unspecified"))
    )
    (net (code "36") (name "/M_AL") (class "Default")
      (node (ref "TP4") (pin "1") (pinfunction "1_1") (pintype "input"))
      (node (ref "U2") (pin "12") (pinfunction "PA7/PB0/PB1_12") (pintype "input"))
      (node (ref "U8") (pin "4") (pinfunction "LIN1_4") (pintype "unspecified"))
    )
    (net (code "37") (name "/M_BH") (class "Default")
      (node (ref "TP2") (pin "1") (pinfunction "1_1") (pintype "input"))
      (node (ref "U2") (pin "14") (pinfunction "PA9/PA11_14") (pintype "input"))
      (node (ref "U8") (pin "2") (pinfunction "HIN2_2") (pintype "unspecified"))
    )
    (net (code "38") (name "/M_BL") (class "Default")
      (node (ref "TP5") (pin "1") (pinfunction "1_1") (pintype "input"))
      (node (ref "U2") (pin "3") (pinfunction "PF1/HEXT_OUT_3") (pintype "input"))
      (node (ref "U8") (pin "5") (pinfunction "LIN2_5") (pintype "unspecified"))
    )
    (net (code "39") (name "/M_BRK") (class "Default")
      (node (ref "H1") (pin "2") (pinfunction "2_2") (pintype "input"))
      (node (ref "U2") (pin "11") (pinfunction "PA6_11") (pintype "input"))
    )
    (net (code "40") (name "/M_CH") (class "Default")
      (node (ref "TP3") (pin "1") (pinfunction "1_1") (pintype "input"))
      (node (ref "U2") (pin "15") (pinfunction "PA10/PA12_15") (pintype "input"))
      (node (ref "U8") (pin "3") (pinfunction "HIN3_3") (pintype "unspecified"))
    )
    (net (code "41") (name "/M_CL") (class "Default")
      (node (ref "TP1") (pin "1") (pinfunction "1_1") (pintype "input"))
      (node (ref "U2") (pin "13") (pinfunction "PA8/PB13/PB14/PB15_13") (pintype "input"))
      (node (ref "U8") (pin "6") (pinfunction "LIN3_6") (pintype "unspecified"))
    )
    (net (code "42") (name "/NRST") (class "Default")
      (node (ref "C4") (pin "1") (pinfunction "1_1") (pintype "unspecified"))
      (node (ref "P1") (pin "5") (pinfunction "5_5") (pintype "input"))
      (node (ref "SW2") (pin "2") (pinfunction "2_2") (pintype "unspecified"))
      (node (ref "U2") (pin "4") (pinfunction "PF2/NRST_4") (pintype "input"))
    )
    (net (code "43") (name "/PWR{slash}SPI_SCK") (class "Default")
      (node (ref "C12") (pin "2") (pinfunction "2_2") (pintype "input"))
      (node (ref "FPC1") (pin "2") (pinfunction "2_2") (pintype "unspecified"))
      (node (ref "R12") (pin "2") (pinfunction "2_2") (pintype "input"))
      (node (ref "R15") (pin "2") (pinfunction "2_2") (pintype "input"))
      (node (ref "U2") (pin "10") (pinfunction "PA5_10") (pintype "input"))
    )
    (net (code "44") (name "/PWR{slash}SPI_SCK_PL") (class "Default")
      (node (ref "FPC3") (pin "7") (pinfunction "7_7") (pintype "unspecified"))
    )
    (net (code "45") (name "/RX") (class "Default")
      (node (ref "P1") (pin "10") (pinfunction "10_10") (pintype "input"))
      (node (ref "U2") (pin "19") (pinfunction "PB4_19") (pintype "input"))
    )
    (net (code "46") (name "/SW_CLK") (class "Default")
      (node (ref "P1") (pin "2") (pinfunction "2_2") (pintype "input"))
      (node (ref "U2") (pin "17") (pinfunction "PA14_17") (pintype "input"))
    )
    (net (code "47") (name "/SW_DIO") (class "Default")
      (node (ref "P1") (pin "1") (pinfunction "1_1") (pintype "input"))
      (node (ref "U2") (pin "16") (pinfunction "PA13_16") (pintype "input"))
    )
    (net (code "48") (name "/TX") (class "Default")
      (node (ref "P1") (pin "9") (pinfunction "9_9") (pintype "input"))
      (node (ref "U2") (pin "18") (pinfunction "PA15/PB3_18") (pintype "input"))
    )
    (net (code "49") (name "/VDD") (class "Default")
      (node (ref "C17") (pin "2") (pinfunction "2_2") (pintype "input"))
      (node (ref "R22") (pin "1") (pinfunction "1_1") (pintype "input"))
      (node (ref "SW3") (pin "1") (pinfunction "1_1") (pintype "unspecified"))
      (node (ref "U5") (pin "1") (pinfunction "VDD_1") (pintype "unspecified"))
    )
    (net (code "50") (name "GND") (class "Default")
      (node (ref "12V") (pin "1") (pinfunction "C_1") (pintype "input"))
      (node (ref "3V3") (pin "1") (pinfunction "C_1") (pintype "input"))
      (node (ref "5V") (pin "1") (pinfunction "C_1") (pintype "input"))
      (node (ref "C1") (pin "2") (pinfunction "2_2") (pintype "input"))
      (node (ref "C12") (pin "1") (pinfunction "1_1") (pintype "input"))
      (node (ref "C13") (pin "1") (pinfunction "1_1") (pintype "input"))
      (node (ref "C14") (pin "1") (pinfunction "1_1") (pintype "input"))
      (node (ref "C15") (pin "1") (pinfunction "1_1") (pintype "input"))
      (node (ref "C16") (pin "1") (pinfunction "1_1") (pintype "input"))
      (node (ref "C17") (pin "1") (pinfunction "1_1") (pintype "input"))
      (node (ref "C18") (pin "2") (pinfunction "2_2") (pintype "input"))
      (node (ref "C2") (pin "2") (pinfunction "2_2") (pintype "input"))
      (node (ref "C3") (pin "1") (pinfunction "1_1") (pintype "input"))
      (node (ref "C4") (pin "2") (pinfunction "2_2") (pintype "unspecified"))
      (node (ref "C5") (pin "2") (pinfunction "2_2") (pintype "unspecified"))
      (node (ref "C6") (pin "1") (pinfunction "1_1") (pintype "unspecified"))
      (node (ref "C7") (pin "2") (pinfunction "2_2") (pintype "unspecified"))
      (node (ref "C8") (pin "1") (pinfunction "1_1") (pintype "unspecified"))
      (node (ref "D1") (pin "1") (pinfunction "A_1") (pintype "unspecified"))
      (node (ref "FPC1") (pin "3") (pinfunction "3_3") (pintype "unspecified"))
      (node (ref "FPC1") (pin "6") (pinfunction "6_6") (pintype "unspecified"))
      (node (ref "FPC2") (pin "7") (pinfunction "7_7") (pintype "unspecified"))
      (node (ref "FPC3") (pin "3") (pinfunction "3_3") (pintype "unspecified"))
      (node (ref "FPC3") (pin "6") (pinfunction "6_6") (pintype "unspecified"))
      (node (ref "OLED1") (pin "1") (pinfunction "GND_1") (pintype "unspecified"))
      (node (ref "P1") (pin "7") (pinfunction "7_7") (pintype "input"))
      (node (ref "P1") (pin "8") (pinfunction "8_8") (pintype "input"))
      (node (ref "Q4") (pin "1") (pinfunction "S_1") (pintype "unspecified"))
      (node (ref "Q4") (pin "2") (pinfunction "S_2") (pintype "unspecified"))
      (node (ref "Q4") (pin "3") (pinfunction "S_3") (pintype "unspecified"))
      (node (ref "Q5") (pin "1") (pinfunction "S_1") (pintype "unspecified"))
      (node (ref "Q5") (pin "2") (pinfunction "S_2") (pintype "unspecified"))
      (node (ref "Q5") (pin "3") (pinfunction "S_3") (pintype "unspecified"))
      (node (ref "Q6") (pin "1") (pinfunction "S_1") (pintype "unspecified"))
      (node (ref "Q6") (pin "2") (pinfunction "S_2") (pintype "unspecified"))
      (node (ref "Q6") (pin "3") (pinfunction "S_3") (pintype "unspecified"))
      (node (ref "R15") (pin "1") (pinfunction "1_1") (pintype "input"))
      (node (ref "R2") (pin "1") (pinfunction "1_1") (pintype "input"))
      (node (ref "R5") (pin "1") (pinfunction "1_1") (pintype "input"))
      (node (ref "SW2") (pin "1") (pinfunction "1_1") (pintype "unspecified"))
      (node (ref "SW3") (pin "3") (pinfunction "3_3") (pintype "unspecified"))
      (node (ref "U1") (pin "5") (pinfunction "GND_5") (pintype "unspecified"))
      (node (ref "U1") (pin "6") (pinfunction "GND_6") (pintype "unspecified"))
      (node (ref "U1") (pin "7") (pinfunction "GND_7") (pintype "unspecified"))
      (node (ref "U1") (pin "8") (pinfunction "GND_8") (pintype "unspecified"))
      (node (ref "U2") (pin "24") (pinfunction "VSS/VSSA_24") (pintype "input"))
      (node (ref "U4") (pin "2") (pinfunction "GND_2") (pintype "input"))
      (node (ref "U5") (pin "11") (pinfunction "GND_11") (pintype "unspecified"))
      (node (ref "U5") (pin "2") (pinfunction "CFG2_2") (pintype "unspecified"))
      (node (ref "U5") (pin "9") (pinfunction "CFG1_9") (pintype "unspecified"))
      (node (ref "U6") (pin "4") (pinfunction "GND_4") (pintype "unspecified"))
      (node (ref "U7") (pin "C") (pinfunction "C_C") (pintype "unspecified"))
      (node (ref "U8") (pin "8") (pinfunction "COM_8") (pintype "unspecified"))
      (node (ref "USB1") (pin "1") (pinfunction "EP_1") (pintype "unspecified"))
      (node (ref "USB1") (pin "2") (pinfunction "EP_2") (pintype "unspecified"))
      (node (ref "USB1") (pin "3") (pinfunction "EP_3") (pintype "unspecified"))
      (node (ref "USB1") (pin "4") (pinfunction "EP_4") (pintype "unspecified"))
      (node (ref "USB1") (pin "A1") (pinfunction "GND_A1") (pintype "unspecified"))
      (node (ref "USB1") (pin "A12") (pinfunction "GND_A12") (pintype "unspecified"))
      (node (ref "USB1") (pin "B1") (pinfunction "GND_B1") (pintype "unspecified"))
      (node (ref "USB1") (pin "B12") (pinfunction "GND_B12") (pintype "unspecified"))
    )
    (net (code "51") (name "Net-(3V3-A)") (class "Default")
      (node (ref "3V3") (pin "2") (pinfunction "A_2") (pintype "input"))
      (node (ref "R23") (pin "2") (pinfunction "2_2") (pintype "input"))
    )
    (net (code "52") (name "Net-(5V-A)") (class "Default")
      (node (ref "5V") (pin "2") (pinfunction "A_2") (pintype "input"))
      (node (ref "R24") (pin "2") (pinfunction "2_2") (pintype "input"))
    )
    (net (code "53") (name "Net-(12V-A)") (class "Default")
      (node (ref "12V") (pin "2") (pinfunction "A_2") (pintype "input"))
      (node (ref "R25") (pin "2") (pinfunction "2_2") (pintype "input"))
    )
    (net (code "54") (name "Net-(D1-K)") (class "Default")
      (node (ref "D1") (pin "2") (pinfunction "K_2") (pintype "unspecified"))
      (node (ref "L1") (pin "2") (pinfunction "2_2") (pintype "unspecified"))
      (node (ref "U1") (pin "2") (pinfunction "OUTPUT_2") (pintype "unspecified"))
    )
    (net (code "55") (name "Net-(H1-Pad1)") (class "Default")
      (node (ref "H1") (pin "1") (pinfunction "1_1") (pintype "input"))
      (node (ref "R1") (pin "2") (pinfunction "2_2") (pintype "input"))
    )
    (net (code "56") (name "Net-(H1-Pad3)") (class "Default")
      (node (ref "H1") (pin "3") (pinfunction "3_3") (pintype "input"))
      (node (ref "R2") (pin "2") (pinfunction "2_2") (pintype "input"))
    )
    (net (code "57") (name "Net-(MCU-A)") (class "Default")
      (node (ref "MCU") (pin "2") (pinfunction "A_2") (pintype "input"))
      (node (ref "R5") (pin "2") (pinfunction "2_2") (pintype "input"))
    )
    (net (code "58") (name "Net-(Q1-G)") (class "Default")
      (node (ref "Q1") (pin "4") (pinfunction "G_4") (pintype "unspecified"))
      (node (ref "R6") (pin "1") (pinfunction "1_1") (pintype "input"))
    )
    (net (code "59") (name "Net-(Q2-G)") (class "Default")
      (node (ref "Q2") (pin "4") (pinfunction "G_4") (pintype "unspecified"))
      (node (ref "R7") (pin "1") (pinfunction "1_1") (pintype "input"))
    )
    (net (code "60") (name "Net-(Q3-G)") (class "Default")
      (node (ref "Q3") (pin "4") (pinfunction "G_4") (pintype "unspecified"))
      (node (ref "R8") (pin "1") (pinfunction "1_1") (pintype "input"))
    )
    (net (code "61") (name "Net-(Q4-G)") (class "Default")
      (node (ref "Q4") (pin "4") (pinfunction "G_4") (pintype "unspecified"))
      (node (ref "R9") (pin "1") (pinfunction "1_1") (pintype "input"))
    )
    (net (code "62") (name "Net-(Q5-G)") (class "Default")
      (node (ref "Q5") (pin "4") (pinfunction "G_4") (pintype "unspecified"))
      (node (ref "R10") (pin "1") (pinfunction "1_1") (pintype "input"))
    )
    (net (code "63") (name "Net-(Q6-G)") (class "Default")
      (node (ref "Q6") (pin "4") (pinfunction "G_4") (pintype "unspecified"))
      (node (ref "R11") (pin "1") (pinfunction "1_1") (pintype "input"))
    )
    (net (code "64") (name "Net-(R14-Pad1)") (class "Default")
      (node (ref "R14") (pin "1") (pinfunction "1_1") (pintype "unspecified"))
      (node (ref "R16") (pin "1") (pinfunction "1_1") (pintype "unspecified"))
      (node (ref "U7") (pin "S") (pinfunction "S_S") (pintype "unspecified"))
    )
    (net (code "65") (name "Net-(R17-Pad1)") (class "Default")
      (node (ref "R17") (pin "1") (pinfunction "1_1") (pintype "unspecified"))
      (node (ref "R18") (pin "1") (pinfunction "1_1") (pintype "unspecified"))
      (node (ref "U7") (pin "B") (pinfunction "B_B") (pintype "unspecified"))
    )
    (net (code "66") (name "Net-(R19-Pad1)") (class "Default")
      (node (ref "R19") (pin "1") (pinfunction "1_1") (pintype "unspecified"))
      (node (ref "R20") (pin "1") (pinfunction "1_1") (pintype "unspecified"))
      (node (ref "U7") (pin "A") (pinfunction "A_A") (pintype "unspecified"))
    )
    (net (code "67") (name "Net-(U5-VBUS)") (class "Default")
      (node (ref "R21") (pin "2") (pinfunction "2_2") (pintype "input"))
      (node (ref "U5") (pin "8") (pinfunction "VBUS_8") (pintype "unspecified"))
    )
    (net (code "68") (name "unconnected-(FPC1-Pad9)") (class "Default")
      (node (ref "FPC1") (pin "9") (pinfunction "9_9") (pintype "unspecified+no_connect"))
    )
    (net (code "69") (name "unconnected-(FPC1-Pad10)") (class "Default")
      (node (ref "FPC1") (pin "10") (pinfunction "10_10") (pintype "unspecified+no_connect"))
    )
    (net (code "70") (name "unconnected-(FPC2-Pad13)") (class "Default")
      (node (ref "FPC2") (pin "13") (pinfunction "13_13") (pintype "unspecified+no_connect"))
    )
    (net (code "71") (name "unconnected-(FPC2-Pad14)") (class "Default")
      (node (ref "FPC2") (pin "14") (pinfunction "14_14") (pintype "unspecified+no_connect"))
    )
    (net (code "72") (name "unconnected-(FPC3-Pad9)") (class "Default")
      (node (ref "FPC3") (pin "9") (pinfunction "9_9") (pintype "unspecified+no_connect"))
    )
    (net (code "73") (name "unconnected-(FPC3-Pad10)") (class "Default")
      (node (ref "FPC3") (pin "10") (pinfunction "10_10") (pintype "unspecified+no_connect"))
    )
    (net (code "74") (name "unconnected-(P1-Pad3)") (class "Default")
      (node (ref "P1") (pin "3") (pinfunction "3_3") (pintype "input+no_connect"))
    )
    (net (code "75") (name "unconnected-(P1-Pad4)") (class "Default")
      (node (ref "P1") (pin "4") (pinfunction "4_4") (pintype "input+no_connect"))
    )
    (net (code "76") (name "unconnected-(SCREW1-Pad1)") (class "Default")
      (node (ref "SCREW1") (pin "1") (pinfunction "1_1") (pintype "input"))
    )
    (net (code "77") (name "unconnected-(SCREW2-Pad1)") (class "Default")
      (node (ref "SCREW2") (pin "1") (pinfunction "1_1") (pintype "input"))
    )
    (net (code "78") (name "unconnected-(SCREW3-Pad1)") (class "Default")
      (node (ref "SCREW3") (pin "1") (pinfunction "1_1") (pintype "input"))
    )
    (net (code "79") (name "unconnected-(SCREW4-Pad1)") (class "Default")
      (node (ref "SCREW4") (pin "1") (pinfunction "1_1") (pintype "input"))
    )
    (net (code "80") (name "unconnected-(U1-ON{slash}OFF-Pad4)") (class "Default")
      (node (ref "U1") (pin "4") (pinfunction "ON/OFF_4") (pintype "unspecified+no_connect"))
    )
    (net (code "81") (name "unconnected-(U4-NC-Pad4)") (class "Default")
      (node (ref "U4") (pin "4") (pinfunction "NC_4") (pintype "input+no_connect"))
    )
    (net (code "82") (name "unconnected-(U5-PG-Pad10)") (class "Default")
      (node (ref "U5") (pin "10") (pinfunction "PG_10") (pintype "unspecified+no_connect"))
    )
    (net (code "83") (name "unconnected-(U6-NC-Pad1)") (class "Default")
      (node (ref "U6") (pin "1") (pinfunction "NC_1") (pintype "unspecified+no_connect"))
    )
    (net (code "84") (name "unconnected-(U7-Pad0)") (class "Default")
      (node (ref "U7") (pin "0") (pinfunction "0_0") (pintype "unspecified+no_connect"))
    )
    (net (code "85") (name "unconnected-(USB1-SBU1-PadA8)") (class "Default")
      (node (ref "USB1") (pin "A8") (pinfunction "SBU1_A8") (pintype "unspecified+no_connect"))
    )
    (net (code "86") (name "unconnected-(USB1-SBU2-PadB8)") (class "Default")
      (node (ref "USB1") (pin "B8") (pinfunction "SBU2_B8") (pintype "unspecified+no_connect"))
    )
  )
)
